# MCU_STM32F103RBT6.net
KiCad netlist of a schematic drawn in Altium Designer
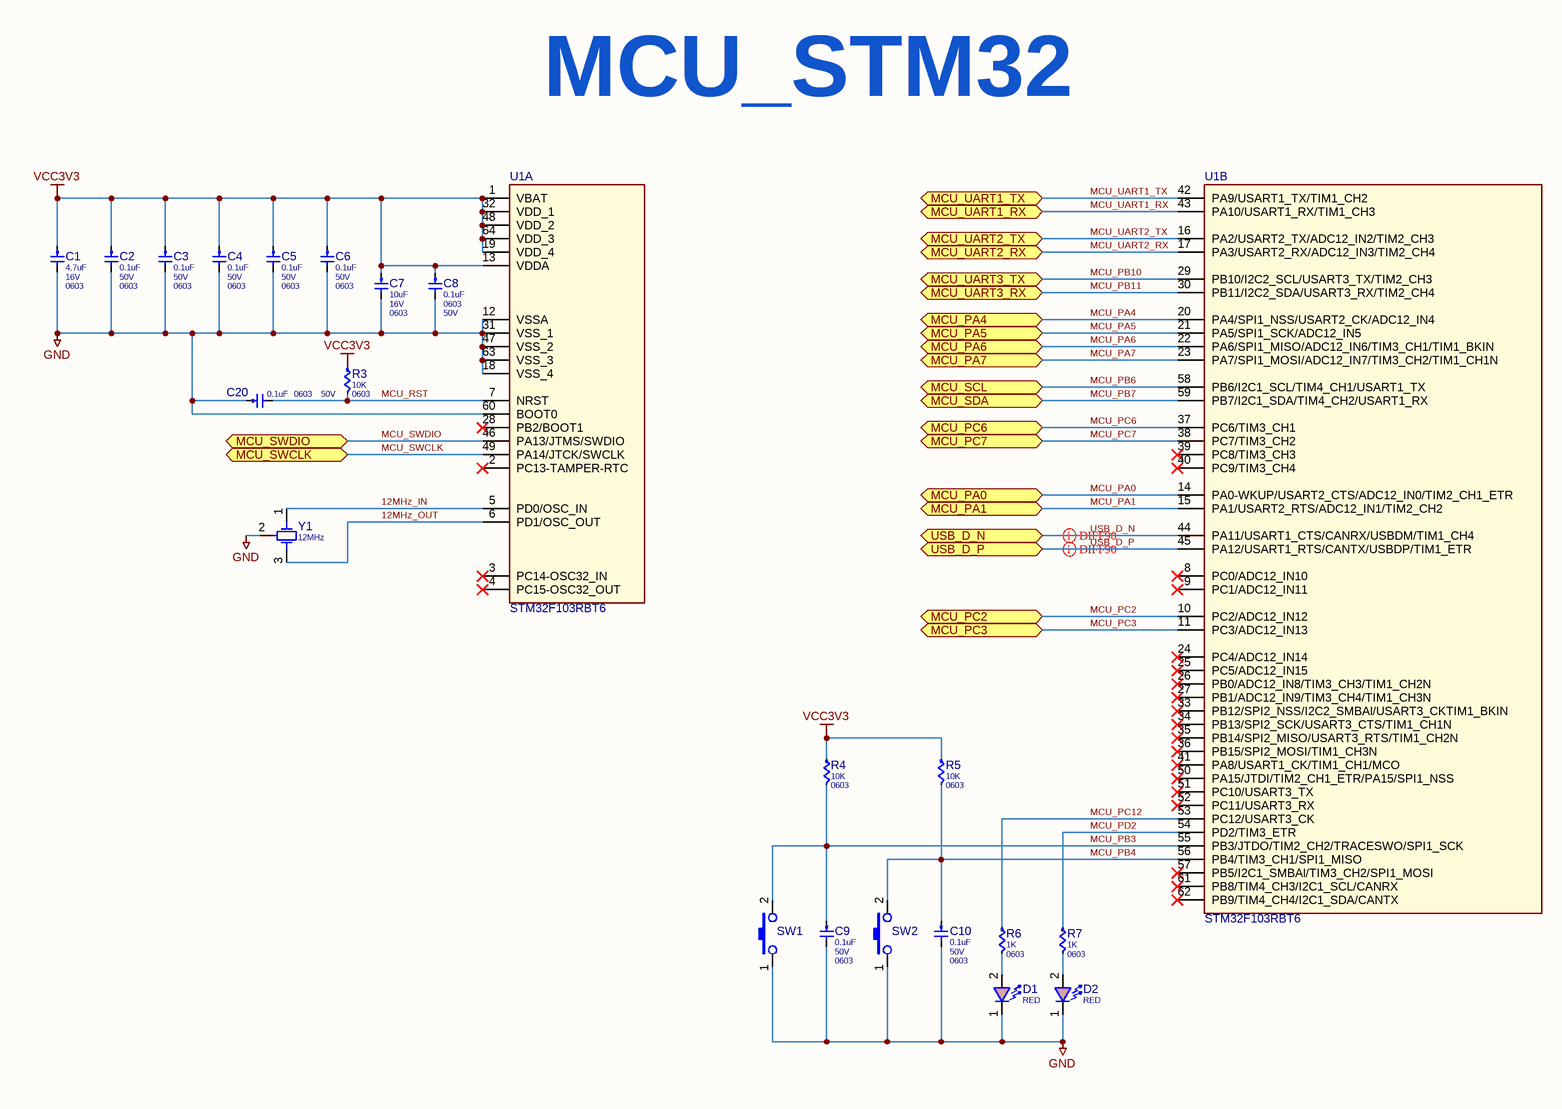
[diagram p0: MCU_STM32F103RBT6.SchDoc]

(export (version "E")
  (design (tool "Eeschema 10.0.6"))
  (components
    (comp (ref "C1")
      (value "4.7uF")
      (footprint "C0603")
      (description "CAP CER 4.7UF 20% 16V X5R 0603 SMD")
      (fields
        (field (name "TOLERANCE") "20%")
        (field (name "VOLTAGE") "16V")
        (field (name "PACK") "0603")
        (field (name "Comment") "4.7uF 16V 0603")
      )
      (libsource (lib "FENIKAA_LIB") (part "C0603_4.7uF_16V_20%"))
    )
    (comp (ref "C2")
      (value "0.1uF")
      (footprint "C0603")
      (description "CAP CER 0.1UF 10% 50V X7R 0603 SMD")
      (fields
        (field (name "TOLERANCE") "10%")
        (field (name "VOLTAGE") "50V")
        (field (name "PACK") "0603")
        (field (name "Comment") "0.1uF 50V 0603")
      )
      (libsource (lib "FENIKAA_LIB") (part "C0603_0.1uF_50V_10%"))
    )
    (comp (ref "C3")
      (value "0.1uF")
      (footprint "C0603")
      (description "CAP CER 0.1UF 10% 50V X7R 0603 SMD")
      (fields
        (field (name "TOLERANCE") "10%")
        (field (name "VOLTAGE") "50V")
        (field (name "PACK") "0603")
        (field (name "Comment") "0.1uF 50V 0603")
      )
      (libsource (lib "FENIKAA_LIB") (part "C0603_0.1uF_50V_10%"))
    )
    (comp (ref "C4")
      (value "0.1uF")
      (footprint "C0603")
      (description "CAP CER 0.1UF 10% 50V X7R 0603 SMD")
      (fields
        (field (name "TOLERANCE") "10%")
        (field (name "VOLTAGE") "50V")
        (field (name "PACK") "0603")
        (field (name "Comment") "0.1uF 50V 0603")
      )
      (libsource (lib "FENIKAA_LIB") (part "C0603_0.1uF_50V_10%"))
    )
    (comp (ref "C5")
      (value "0.1uF")
      (footprint "C0603")
      (description "CAP CER 0.1UF 10% 50V X7R 0603 SMD")
      (fields
        (field (name "TOLERANCE") "10%")
        (field (name "VOLTAGE") "50V")
        (field (name "PACK") "0603")
        (field (name "Comment") "0.1uF 50V 0603")
      )
      (libsource (lib "FENIKAA_LIB") (part "C0603_0.1uF_50V_10%"))
    )
    (comp (ref "C6")
      (value "0.1uF")
      (footprint "C0603")
      (description "CAP CER 0.1UF 10% 50V X7R 0603 SMD")
      (fields
        (field (name "TOLERANCE") "10%")
        (field (name "VOLTAGE") "50V")
        (field (name "PACK") "0603")
        (field (name "Comment") "0.1uF 50V 0603")
      )
      (libsource (lib "FENIKAA_LIB") (part "C0603_0.1uF_50V_10%"))
    )
    (comp (ref "C7")
      (value "10uF")
      (footprint "C0603")
      (description "CAP CER 10UF 10% 16V X5R 0603 SMD")
      (fields
        (field (name "TOLERANCE") "10%")
        (field (name "VOLTAGE") "16V")
        (field (name "PACK") "0603")
        (field (name "Comment") "10uF 16V 0603")
      )
      (libsource (lib "FENIKAA_LIB") (part "C0603_10uF_16V_10%"))
    )
    (comp (ref "C8")
      (value "0.1uF")
      (footprint "C0603")
      (description "CAP CER 0.1UF 10% 50V X7R 0603 SMD")
      (fields
        (field (name "TOLERANCE") "10%")
        (field (name "PACK") "0603")
        (field (name "VOLTAGE") "50V")
        (field (name "Comment") "0.1uF 50V 0603")
      )
      (libsource (lib "FENIKAA_LIB") (part "C0603_0.1uF_50V_10%"))
    )
    (comp (ref "C9")
      (value "0.1uF")
      (footprint "C0603")
      (description "CAP CER 0.1UF 10% 50V X7R 0603 SMD")
      (fields
        (field (name "TOLERANCE") "10%")
        (field (name "VOLTAGE") "50V")
        (field (name "PACK") "0603")
        (field (name "Comment") "0.1uF 50V 0603")
      )
      (libsource (lib "FENIKAA_LIB") (part "C0603_0.1uF_50V_10%"))
    )
    (comp (ref "C10")
      (value "0.1uF")
      (footprint "C0603")
      (description "CAP CER 0.1UF 10% 50V X7R 0603 SMD")
      (fields
        (field (name "TOLERANCE") "10%")
        (field (name "VOLTAGE") "50V")
        (field (name "PACK") "0603")
        (field (name "Comment") "0.1uF 50V 0603")
      )
      (libsource (lib "FENIKAA_LIB") (part "C0603_0.1uF_50V_10%"))
    )
    (comp (ref "C20")
      (value "0.1uF")
      (footprint "C0603")
      (description "CAP CER 0.1UF 10% 50V X7R 0603 SMD")
      (fields
        (field (name "TOLERANCE") "10%")
        (field (name "PACK") "0603")
        (field (name "VOLTAGE") "50V")
        (field (name "Comment") "0.1uF 50V 0603")
      )
      (libsource (lib "FENIKAA_LIB") (part "C0603_0.1uF_50V_10%"))
    )
    (comp (ref "D1")
      (value "LH R974-LP-1")
      (footprint "LED0805_RED")
      (description "LED IND RED 1.8V 20mA 0805 SMD")
      (fields (field (name "COLOR") "RED"))
      (libsource (lib "FENIKAA_LIB") (part "LED0805_RED"))
    )
    (comp (ref "D2")
      (value "LH R974-LP-1")
      (footprint "LED0805_RED")
      (description "LED IND RED 1.8V 20mA 0805 SMD")
      (fields (field (name "COLOR") "RED"))
      (libsource (lib "FENIKAA_LIB") (part "LED0805_RED"))
    )
    (comp (ref "R3")
      (value "10K")
      (footprint "R0603")
      (description "RES CHP 10K 1% 1/10W 0603 SMD")
      (fields (field (name "POWER") "1/10W") (field (name "PACK") "0603") (field (name "TOLERANCE") "1%"))
      (libsource (lib "FENIKAA_LIB") (part "R0603_10K_1/10W_1%"))
    )
    (comp (ref "R4")
      (value "10K")
      (footprint "R0603")
      (description "RES CHP 10K 1% 1/10W 0603 SMD")
      (fields (field (name "POWER") "1/10W") (field (name "PACK") "0603") (field (name "TOLERANCE") "1%"))
      (libsource (lib "FENIKAA_LIB") (part "R0603_10K_1/10W_1%"))
    )
    (comp (ref "R5")
      (value "10K")
      (footprint "R0603")
      (description "RES CHP 10K 1% 1/10W 0603 SMD")
      (fields (field (name "POWER") "1/10W") (field (name "PACK") "0603") (field (name "TOLERANCE") "1%"))
      (libsource (lib "FENIKAA_LIB") (part "R0603_10K_1/10W_1%"))
    )
    (comp (ref "R6")
      (value "1K")
      (footprint "R0603")
      (description "RES CHP 1K 1% 1/10W 0603 SMD")
      (fields (field (name "POWER") "1/10W") (field (name "PACK") "0603") (field (name "TOLERANCE") "1%"))
      (libsource (lib "FENIKAA_LIB") (part "R0603_1K_1/10W_1%"))
    )
    (comp (ref "R7")
      (value "1K")
      (footprint "R0603")
      (description "RES CHP 1K 1% 1/10W 0603 SMD")
      (fields (field (name "POWER") "1/10W") (field (name "PACK") "0603") (field (name "TOLERANCE") "1%"))
      (libsource (lib "FENIKAA_LIB") (part "R0603_1K_1/10W_1%"))
    )
    (comp (ref "SW1")
      (value "BTN 3x6x5 SMD")
      (footprint "BTN_6L3W5H")
      (description "SWT BTN 3x6x5 SMD")
      (libsource (lib "FENIKAA_LIB") (part "SWT_BTN_3x6x5"))
    )
    (comp (ref "SW2")
      (value "BTN 3x6x5 SMD")
      (footprint "BTN_6L3W5H")
      (description "SWT BTN 3x6x5 SMD")
      (libsource (lib "FENIKAA_LIB") (part "SWT_BTN_3x6x5"))
    )
    (comp (ref "U1")
      (value "STM32F103RBT6")
      (footprint "64LQFP")
      (description "ICS EMB MCU 32BIT 128KB FLASH 64LQFP SMD")
      (fields (field (name "VOLTAGE") "2~3.6V") (field (name "MGR PN") "STM32F103RBT6"))
      (libsource (lib "FENIKAA_LIB") (part "IC_STM32F103RBT6"))
    )
    (comp (ref "Y1")
      (value "12MHz")
      (footprint "CRYS_3-SMD")
      (description "CRYSTAL 12MHZ 33PF 3.2L1.3W0.8H SMD")
      (fields (field (name "Comment") "CSTNE12M0G550000R0"))
      (libsource (lib "FENIKAA_LIB") (part "CRYS_CSTNE12M0G550000R0"))
    )
  )
  (nets
    (net (code "1") (name "/12MHz_IN") (class "Default")
      (node (ref "U1") (pin "5") (pinfunction "PD0/OSC_IN_5") (pintype "passive"))
      (node (ref "Y1") (pin "1") (pinfunction "IN_1") (pintype "passive"))
    )
    (net (code "2") (name "/12MHz_OUT") (class "Default")
      (node (ref "U1") (pin "6") (pinfunction "PD1/OSC_OUT_6") (pintype "passive"))
      (node (ref "Y1") (pin "3") (pinfunction "OUT_3") (pintype "passive"))
    )
    (net (code "3") (name "/MCU_PA0") (class "Default")
      (node (ref "U1") (pin "14") (pinfunction "PA0-WKUP/USART2_CTS/ADC12_IN0/TIM2_CH1_ETR_14") (pintype "passive"))
    )
    (net (code "4") (name "/MCU_PA1") (class "Default")
      (node (ref "U1") (pin "15") (pinfunction "PA1/USART2_RTS/ADC12_IN1/TIM2_CH2_15") (pintype "passive"))
    )
    (net (code "5") (name "/MCU_PA4") (class "Default")
      (node (ref "U1") (pin "20") (pinfunction "PA4/SPI1_NSS/USART2_CK/ADC12_IN4_20") (pintype "passive"))
    )
    (net (code "6") (name "/MCU_PA5") (class "Default")
      (node (ref "U1") (pin "21") (pinfunction "PA5/SPI1_SCK/ADC12_IN5_21") (pintype "passive"))
    )
    (net (code "7") (name "/MCU_PA6") (class "Default")
      (node (ref "U1") (pin "22") (pinfunction "PA6/SPI1_MISO/ADC12_IN6/TIM3_CH1/TIM1_BKIN_22") (pintype "passive"))
    )
    (net (code "8") (name "/MCU_PA7") (class "Default")
      (node (ref "U1") (pin "23") (pinfunction "PA7/SPI1_MOSI/ADC12_IN7/TIM3_CH2/TIM1_CH1N_23") (pintype "passive"))
    )
    (net (code "9") (name "/MCU_PB3") (class "Default")
      (node (ref "C9") (pin "1") (pinfunction "1_1") (pintype "passive"))
      (node (ref "R4") (pin "2") (pinfunction "2_2") (pintype "passive"))
      (node (ref "SW1") (pin "2") (pinfunction "3,4_2") (pintype "passive"))
      (node (ref "U1") (pin "55") (pinfunction "PB3/JTDO/TIM2_CH2/TRACESWO/SPI1_SCK_55") (pintype "passive"))
    )
    (net (code "10") (name "/MCU_PB4") (class "Default")
      (node (ref "C10") (pin "1") (pinfunction "1_1") (pintype "passive"))
      (node (ref "R5") (pin "2") (pinfunction "2_2") (pintype "passive"))
      (node (ref "SW2") (pin "2") (pinfunction "3,4_2") (pintype "passive"))
      (node (ref "U1") (pin "56") (pinfunction "PB4/TIM3_CH1/SPI1_MISO_56") (pintype "passive"))
    )
    (net (code "11") (name "/MCU_PB6") (class "Default")
      (node (ref "U1") (pin "58") (pinfunction "PB6/I2C1_SCL/TIM4_CH1/USART1_TX_58") (pintype "passive"))
    )
    (net (code "12") (name "/MCU_PB7") (class "Default")
      (node (ref "U1") (pin "59") (pinfunction "PB7/I2C1_SDA/TIM4_CH2/USART1_RX_59") (pintype "passive"))
    )
    (net (code "13") (name "/MCU_PB10") (class "Default")
      (node (ref "U1") (pin "29") (pinfunction "PB10/I2C2_SCL/USART3_TX/TIM2_CH3_29") (pintype "passive"))
    )
    (net (code "14") (name "/MCU_PB11") (class "Default")
      (node (ref "U1") (pin "30") (pinfunction "PB11/I2C2_SDA/USART3_RX/TIM2_CH4_30") (pintype "passive"))
    )
    (net (code "15") (name "/MCU_PC2") (class "Default")
      (node (ref "U1") (pin "10") (pinfunction "PC2/ADC12_IN12_10") (pintype "passive"))
    )
    (net (code "16") (name "/MCU_PC3") (class "Default")
      (node (ref "U1") (pin "11") (pinfunction "PC3/ADC12_IN13_11") (pintype "passive"))
    )
    (net (code "17") (name "/MCU_PC6") (class "Default")
      (node (ref "U1") (pin "37") (pinfunction "PC6/TIM3_CH1_37") (pintype "passive"))
    )
    (net (code "18") (name "/MCU_PC7") (class "Default")
      (node (ref "U1") (pin "38") (pinfunction "PC7/TIM3_CH2_38") (pintype "passive"))
    )
    (net (code "19") (name "/MCU_PC12") (class "Default")
      (node (ref "R6") (pin "1") (pinfunction "1_1") (pintype "passive"))
      (node (ref "U1") (pin "53") (pinfunction "PC12/USART3_CK_53") (pintype "passive"))
    )
    (net (code "20") (name "/MCU_PD2") (class "Default")
      (node (ref "R7") (pin "1") (pinfunction "1_1") (pintype "passive"))
      (node (ref "U1") (pin "54") (pinfunction "PD2/TIM3_ETR_54") (pintype "passive"))
    )
    (net (code "21") (name "/MCU_RST") (class "Default")
      (node (ref "C20") (pin "2") (pinfunction "2_2") (pintype "passive"))
      (node (ref "R3") (pin "2") (pinfunction "2_2") (pintype "passive"))
      (node (ref "U1") (pin "7") (pinfunction "NRST_7") (pintype "passive"))
    )
    (net (code "22") (name "/MCU_SWCLK") (class "Default")
      (node (ref "U1") (pin "49") (pinfunction "PA14/JTCK/SWCLK_49") (pintype "passive"))
    )
    (net (code "23") (name "/MCU_SWDIO") (class "Default")
      (node (ref "U1") (pin "46") (pinfunction "PA13/JTMS/SWDIO_46") (pintype "passive"))
    )
    (net (code "24") (name "/MCU_UART1_RX") (class "Default")
      (node (ref "U1") (pin "43") (pinfunction "PA10/USART1_RX/TIM1_CH3_43") (pintype "passive"))
    )
    (net (code "25") (name "/MCU_UART1_TX") (class "Default")
      (node (ref "U1") (pin "42") (pinfunction "PA9/USART1_TX/TIM1_CH2_42") (pintype "passive"))
    )
    (net (code "26") (name "/MCU_UART2_RX") (class "Default")
      (node (ref "U1") (pin "17") (pinfunction "PA3/USART2_RX/ADC12_IN3/TIM2_CH4_17") (pintype "passive"))
    )
    (net (code "27") (name "/MCU_UART2_TX") (class "Default")
      (node (ref "U1") (pin "16") (pinfunction "PA2/USART2_TX/ADC12_IN2/TIM2_CH3_16") (pintype "passive"))
    )
    (net (code "28") (name "/USB_D_N") (class "Default")
      (node (ref "U1") (pin "44") (pinfunction "PA11/USART1_CTS/CANRX/USBDM/TIM1_CH4_44") (pintype "passive"))
    )
    (net (code "29") (name "/USB_D_P") (class "Default")
      (node (ref "U1") (pin "45") (pinfunction "PA12/USART1_RTS/CANTX/USBDP/TIM1_ETR_45") (pintype "passive"))
    )
    (net (code "30") (name "GND") (class "Default")
      (node (ref "C1") (pin "2") (pinfunction "2_2") (pintype "passive"))
      (node (ref "C10") (pin "2") (pinfunction "2_2") (pintype "passive"))
      (node (ref "C2") (pin "2") (pinfunction "2_2") (pintype "passive"))
      (node (ref "C20") (pin "1") (pinfunction "1_1") (pintype "passive"))
      (node (ref "C3") (pin "2") (pinfunction "2_2") (pintype "passive"))
      (node (ref "C4") (pin "2") (pinfunction "2_2") (pintype "passive"))
      (node (ref "C5") (pin "2") (pinfunction "2_2") (pintype "passive"))
      (node (ref "C6") (pin "2") (pinfunction "2_2") (pintype "passive"))
      (node (ref "C7") (pin "2") (pinfunction "2_2") (pintype "passive"))
      (node (ref "C8") (pin "2") (pinfunction "2_2") (pintype "passive"))
      (node (ref "C9") (pin "2") (pinfunction "2_2") (pintype "passive"))
      (node (ref "D1") (pin "1") (pinfunction "K_1") (pintype "passive"))
      (node (ref "D2") (pin "1") (pinfunction "K_1") (pintype "passive"))
      (node (ref "SW1") (pin "1") (pinfunction "1,2_1") (pintype "passive"))
      (node (ref "SW2") (pin "1") (pinfunction "1,2_1") (pintype "passive"))
      (node (ref "U1") (pin "12") (pinfunction "VSSA_12") (pintype "passive"))
      (node (ref "U1") (pin "18") (pinfunction "VSS_4_18") (pintype "passive"))
      (node (ref "U1") (pin "31") (pinfunction "VSS_1_31") (pintype "passive"))
      (node (ref "U1") (pin "47") (pinfunction "VSS_2_47") (pintype "passive"))
      (node (ref "U1") (pin "60") (pinfunction "BOOT0_60") (pintype "passive"))
      (node (ref "U1") (pin "63") (pinfunction "VSS_3_63") (pintype "passive"))
      (node (ref "Y1") (pin "2") (pinfunction "GND_2") (pintype "passive"))
    )
    (net (code "31") (name "Net-(D1-A)") (class "Default")
      (node (ref "D1") (pin "2") (pinfunction "A_2") (pintype "passive"))
      (node (ref "R6") (pin "2") (pinfunction "2_2") (pintype "passive"))
    )
    (net (code "32") (name "Net-(D2-A)") (class "Default")
      (node (ref "D2") (pin "2") (pinfunction "A_2") (pintype "passive"))
      (node (ref "R7") (pin "2") (pinfunction "2_2") (pintype "passive"))
    )
    (net (code "33") (name "VCC3V3") (class "Default")
      (node (ref "C1") (pin "1") (pinfunction "1_1") (pintype "passive"))
      (node (ref "C2") (pin "1") (pinfunction "1_1") (pintype "passive"))
      (node (ref "C3") (pin "1") (pinfunction "1_1") (pintype "passive"))
      (node (ref "C4") (pin "1") (pinfunction "1_1") (pintype "passive"))
      (node (ref "C5") (pin "1") (pinfunction "1_1") (pintype "passive"))
      (node (ref "C6") (pin "1") (pinfunction "1_1") (pintype "passive"))
      (node (ref "C7") (pin "1") (pinfunction "1_1") (pintype "passive"))
      (node (ref "C8") (pin "1") (pinfunction "1_1") (pintype "passive"))
      (node (ref "R3") (pin "1") (pinfunction "1_1") (pintype "passive"))
      (node (ref "R4") (pin "1") (pinfunction "1_1") (pintype "passive"))
      (node (ref "R5") (pin "1") (pinfunction "1_1") (pintype "passive"))
      (node (ref "U1") (pin "1") (pinfunction "VBAT_1") (pintype "passive"))
      (node (ref "U1") (pin "13") (pinfunction "VDDA_13") (pintype "passive"))
      (node (ref "U1") (pin "19") (pinfunction "VDD_4_19") (pintype "passive"))
      (node (ref "U1") (pin "32") (pinfunction "VDD_1_32") (pintype "passive"))
      (node (ref "U1") (pin "48") (pinfunction "VDD_2_48") (pintype "passive"))
      (node (ref "U1") (pin "64") (pinfunction "VDD_3_64") (pintype "passive"))
    )
    (net (code "34") (name "unconnected-(U1A-PB2{slash}BOOT1-Pad28)") (class "Default")
      (node (ref "U1") (pin "28") (pinfunction "PB2/BOOT1_28") (pintype "passive+no_connect"))
    )
    (net (code "35") (name "unconnected-(U1A-PC13-TAMPER-RTC-Pad2)") (class "Default")
      (node (ref "U1") (pin "2") (pinfunction "PC13-TAMPER-RTC_2") (pintype "passive+no_connect"))
    )
    (net (code "36") (name "unconnected-(U1A-PC14-OSC32_IN-Pad3)") (class "Default")
      (node (ref "U1") (pin "3") (pinfunction "PC14-OSC32_IN_3") (pintype "passive+no_connect"))
    )
    (net (code "37") (name "unconnected-(U1A-PC15-OSC32_OUT-Pad4)") (class "Default")
      (node (ref "U1") (pin "4") (pinfunction "PC15-OSC32_OUT_4") (pintype "passive+no_connect"))
    )
    (net (code "38") (name "unconnected-(U1B-PA8{slash}USART1_CK{slash}TIM1_CH1{slash}MCO-Pad41)") (class "Default")
      (node (ref "U1") (pin "41") (pinfunction "PA8/USART1_CK/TIM1_CH1/MCO_41") (pintype "passive+no_connect"))
    )
    (net (code "39") (name "unconnected-(U1B-PA15{slash}JTDI{slash}TIM2_CH1_ETR{slash}PA15{slash}SPI1_NSS-Pad50)") (class "Default")
      (node (ref "U1") (pin "50") (pinfunction "PA15/JTDI/TIM2_CH1_ETR/PA15/SPI1_NSS_50") (pintype "passive+no_connect"))
    )
    (net (code "40") (name "unconnected-(U1B-PB0{slash}ADC12_IN8{slash}TIM3_CH3{slash}TIM1_CH2N-Pad26)") (class "Default")
      (node (ref "U1") (pin "26") (pinfunction "PB0/ADC12_IN8/TIM3_CH3/TIM1_CH2N_26") (pintype "passive+no_connect"))
    )
    (net (code "41") (name "unconnected-(U1B-PB1{slash}ADC12_IN9{slash}TIM3_CH4{slash}TIM1_CH3N-Pad27)") (class "Default")
      (node (ref "U1") (pin "27") (pinfunction "PB1/ADC12_IN9/TIM3_CH4/TIM1_CH3N_27") (pintype "passive+no_connect"))
    )
    (net (code "42") (name "unconnected-(U1B-PB5{slash}I2C1_SMBAl{slash}TIM3_CH2{slash}SPI1_MOSI-Pad57)") (class "Default")
      (node (ref "U1") (pin "57") (pinfunction "PB5/I2C1_SMBAl/TIM3_CH2/SPI1_MOSI_57") (pintype "passive+no_connect"))
    )
    (net (code "43") (name "unconnected-(U1B-PB8{slash}TIM4_CH3{slash}I2C1_SCL{slash}CANRX-Pad61)") (class "Default")
      (node (ref "U1") (pin "61") (pinfunction "PB8/TIM4_CH3/I2C1_SCL/CANRX_61") (pintype "passive+no_connect"))
    )
    (net (code "44") (name "unconnected-(U1B-PB9{slash}TIM4_CH4{slash}I2C1_SDA{slash}CANTX-Pad62)") (class "Default")
      (node (ref "U1") (pin "62") (pinfunction "PB9/TIM4_CH4/I2C1_SDA/CANTX_62") (pintype "passive+no_connect"))
    )
    (net (code "45") (name "unconnected-(U1B-PB12{slash}SPI2_NSS{slash}I2C2_SMBAl{slash}USART3_CKTIM1_BKIN-Pad33)") (class "Default")
      (node (ref "U1") (pin "33") (pinfunction "PB12/SPI2_NSS/I2C2_SMBAl/USART3_CKTIM1_BKIN_33") (pintype "passive+no_connect"))
    )
    (net (code "46") (name "unconnected-(U1B-PB13{slash}SPI2_SCK{slash}USART3_CTS{slash}TIM1_CH1N-Pad34)") (class "Default")
      (node (ref "U1") (pin "34") (pinfunction "PB13/SPI2_SCK/USART3_CTS/TIM1_CH1N_34") (pintype "passive+no_connect"))
    )
    (net (code "47") (name "unconnected-(U1B-PB14{slash}SPI2_MISO{slash}USART3_RTS{slash}TIM1_CH2N-Pad35)") (class "Default")
      (node (ref "U1") (pin "35") (pinfunction "PB14/SPI2_MISO/USART3_RTS/TIM1_CH2N_35") (pintype "passive+no_connect"))
    )
    (net (code "48") (name "unconnected-(U1B-PB15{slash}SPI2_MOSI{slash}TIM1_CH3N-Pad36)") (class "Default")
      (node (ref "U1") (pin "36") (pinfunction "PB15/SPI2_MOSI/TIM1_CH3N_36") (pintype "passive+no_connect"))
    )
    (net (code "49") (name "unconnected-(U1B-PC0{slash}ADC12_IN10-Pad8)") (class "Default")
      (node (ref "U1") (pin "8") (pinfunction "PC0/ADC12_IN10_8") (pintype "passive+no_connect"))
    )
    (net (code "50") (name "unconnected-(U1B-PC1{slash}ADC12_IN11-Pad9)") (class "Default")
      (node (ref "U1") (pin "9") (pinfunction "PC1/ADC12_IN11_9") (pintype "passive+no_connect"))
    )
    (net (code "51") (name "unconnected-(U1B-PC4{slash}ADC12_IN14-Pad24)") (class "Default")
      (node (ref "U1") (pin "24") (pinfunction "PC4/ADC12_IN14_24") (pintype "passive+no_connect"))
    )
    (net (code "52") (name "unconnected-(U1B-PC5{slash}ADC12_IN15-Pad25)") (class "Default")
      (node (ref "U1") (pin "25") (pinfunction "PC5/ADC12_IN15_25") (pintype "passive+no_connect"))
    )
    (net (code "53") (name "unconnected-(U1B-PC8{slash}TIM3_CH3-Pad39)") (class "Default")
      (node (ref "U1") (pin "39") (pinfunction "PC8/TIM3_CH3_39") (pintype "passive+no_connect"))
    )
    (net (code "54") (name "unconnected-(U1B-PC9{slash}TIM3_CH4-Pad40)") (class "Default")
      (node (ref "U1") (pin "40") (pinfunction "PC9/TIM3_CH4_40") (pintype "passive+no_connect"))
    )
    (net (code "55") (name "unconnected-(U1B-PC10{slash}USART3_TX-Pad51)") (class "Default")
      (node (ref "U1") (pin "51") (pinfunction "PC10/USART3_TX_51") (pintype "passive+no_connect"))
    )
    (net (code "56") (name "unconnected-(U1B-PC11{slash}USART3_RX-Pad52)") (class "Default")
      (node (ref "U1") (pin "52") (pinfunction "PC11/USART3_RX_52") (pintype "passive+no_connect"))
    )
  )
)
